# MainBoard.net
KiCad netlist of a schematic drawn in Altium Designer
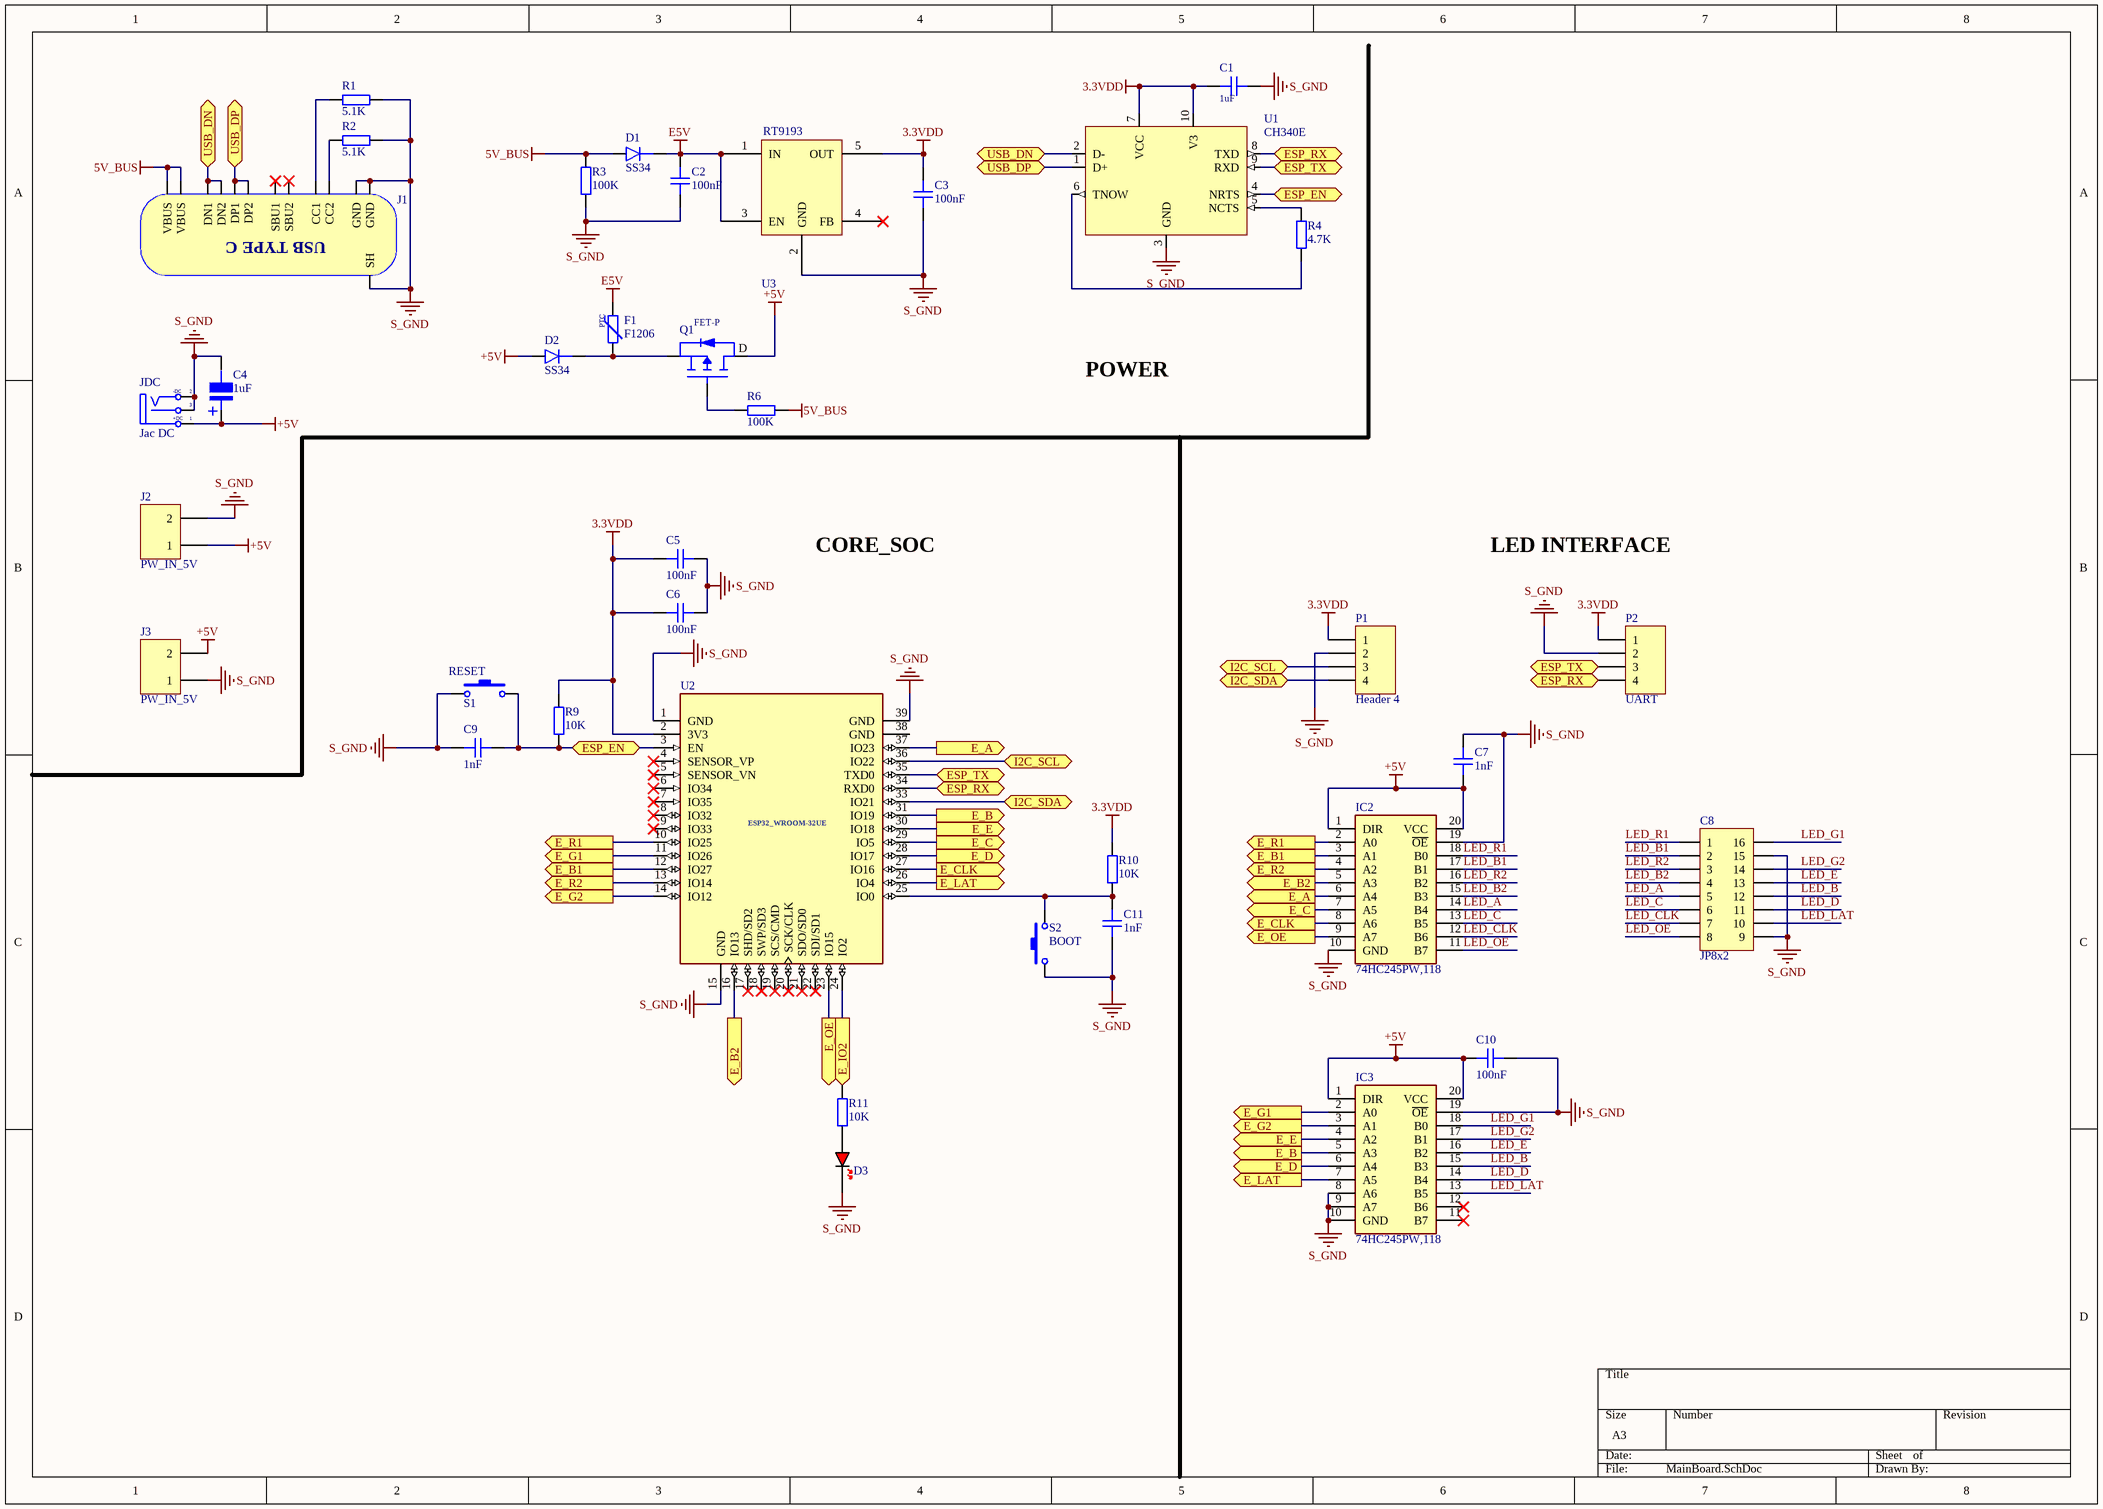
[diagram p0: MainBoard.SchDoc]

(export (version "E")
  (design (tool "Eeschema 10.0.6"))
  (components
    (comp (ref "C1")
      (value "1uF")
      (footprint "CAP_0805")
      (description "Capacitor SMD 0805 50V")
      (libsource (lib "Schematic-Lib-PhilsLab") (part "CAP_0805_50V"))
    )
    (comp (ref "C2")
      (value "100nF")
      (footprint "CAP_0603")
      (description "Capacitor SMD 0603 50V")
      (libsource (lib "Schematic-Lib-PhilsLab") (part "CAP_0603_50V"))
    )
    (comp (ref "C3")
      (value "100nF")
      (footprint "CAP_0603")
      (description "Capacitor SMD 0603 50V")
      (libsource (lib "Schematic-Lib-PhilsLab") (part "CAP_0603_50V"))
    )
    (comp (ref "C4")
      (value "1uF")
      (footprint "tu nhom 4 (B)")
      (description "Dán")
      (libsource (lib "THU VIEN SCH") (part "Tu Nhom 1uF 50V"))
    )
    (comp (ref "C5")
      (value "100nF")
      (footprint "CAP_0603")
      (description "Capacitor SMD 0603 50V")
      (libsource (lib "Schematic-Lib-PhilsLab") (part "CAP_0603_50V"))
    )
    (comp (ref "C6")
      (value "100nF")
      (footprint "CAP_0603")
      (description "Capacitor SMD 0603 50V")
      (libsource (lib "Schematic-Lib-PhilsLab") (part "CAP_0603_50V"))
    )
    (comp (ref "C7")
      (value "1nF")
      (footprint "CAP_0603")
      (description "Capacitor SMD 0603 50V")
      (libsource (lib "Schematic-Lib-PhilsLab") (part "CAP_0603_50V"))
    )
    (comp (ref "C8")
      (value "JP8x2")
      (footprint "JP8-C2T")
      (description "WR-PHD 2.54 mm Dual Socket Header")
      (fields
        (field (name "MANUFACTURER") "Würth Elektronik eiSos GmbH")
        (field (name "PARTNO") "61301621821")
        (field (name "CREATED BY") "Karrer Zheng")
      )
      (libsource (lib "My Library") (part "JP8x2"))
    )
    (comp (ref "C9")
      (value "1nF")
      (footprint "CAP_0603")
      (description "Capacitor SMD 0603 50V")
      (libsource (lib "Schematic-Lib-PhilsLab") (part "CAP_0603_50V"))
    )
    (comp (ref "C10")
      (value "100nF")
      (footprint "CAP_0603")
      (description "Capacitor SMD 0603 50V")
      (libsource (lib "Schematic-Lib-PhilsLab") (part "CAP_0603_50V"))
    )
    (comp (ref "C11")
      (value "1nF")
      (footprint "CAP_0603")
      (description "Capacitor SMD 0603 50V")
      (libsource (lib "Schematic-Lib-PhilsLab") (part "CAP_0603_50V"))
    )
    (comp (ref "D1")
      (value "SS34")
      (footprint "DO-214AC-2 (SMA)")
      (description "Diode SMD SMA (DO-214AA)")
      (libsource (lib "Schematic-Lib-PhilsLab") (part "D_SMA"))
    )
    (comp (ref "D2")
      (value "SS34")
      (footprint "DO-214AC-2 (SMA)")
      (description "Diode SMD SMA (DO-214AA)")
      (libsource (lib "Schematic-Lib-PhilsLab") (part "D_SMA"))
    )
    (comp (ref "D3")
      (value "RED")
      (footprint "LED_0603_RED")
      (description "LED 0603 RED SMD")
      (libsource (lib "Schematic-Lib-PhilsLab") (part "LED_0603_RED"))
    )
    (comp (ref "F1")
      (value "F1206")
      (footprint "FUSE_1206")
      (description "Fuse PPTC SMD 1206")
      (libsource (lib "Schematic-Lib-PhilsLab") (part "FUSE_PPTC_1206"))
    )
    (comp (ref "IC2")
      (value "74HC245PW,118")
      (footprint "74hc245pw")
      (description "Integrated Circuit")
      (fields (field (name "MOUSER PART NUMBER") "771-HC245PW118"))
      (libsource (lib "Digital_Isolator") (part "74HC245PW,118"))
    )
    (comp (ref "IC3")
      (value "74HC245PW,118")
      (footprint "74hc245pw")
      (description "Integrated Circuit")
      (fields (field (name "MOUSER PART NUMBER") "771-HC245PW118"))
      (libsource (lib "Digital_Isolator") (part "74HC245PW,118"))
    )
    (comp (ref "J1")
      (value "TYPE-C-31-M-12")
      (footprint "TYPE-C-31-M-12")
      (description "USB Type C Connector Horizontal SMT")
      (fields (field (name "MANUFACTURER") "Koren Hroparts"))
      (libsource (lib "Schematic-Lib-PhilsLab") (part "TYPE-C-31-M-12"))
    )
    (comp (ref "J2")
      (value "PW_IN_5V")
      (footprint "DOMINO 2L")
      (description "WR-TBL Terminal block - serie 311 - 5.08mm")
      (fields
        (field (name "MANUFACTURER") "Würth Elektronik eiSos GmbH")
        (field (name "PARTNO") "691311500002")
        (field (name "CREATED BY") "Karrer Zheng")
      )
      (libsource (lib "EZTOLOVE") (part "DOMINO2"))
    )
    (comp (ref "J3")
      (value "PW_IN_5V")
      (footprint "DOMINO 2L")
      (description "WR-TBL Terminal block - serie 311 - 5.08mm")
      (fields
        (field (name "MANUFACTURER") "Würth Elektronik eiSos GmbH")
        (field (name "PARTNO") "691311500002")
        (field (name "CREATED BY") "Karrer Zheng")
      )
      (libsource (lib "EZTOLOVE") (part "DOMINO2"))
    )
    (comp (ref "JDC")
      (value "Jac DC")
      (footprint "DC-IN")
      (description "Jac DC input")
      (libsource (lib "EZTOLOVE") (part "DCIN"))
    )
    (comp (ref "P1")
      (value "Header 4")
      (footprint "JP4")
      (description "Header, 4-Pin, Right Angle")
      (fields (field (name "PUBLISHER") "Altium Limited"))
      (libsource (lib "EZTOLOVE") (part "Header 4"))
    )
    (comp (ref "P2")
      (value "UART")
      (footprint "JP4")
      (description "Header, 4-Pin, Right Angle")
      (fields (field (name "PUBLISHER") "Altium Limited"))
      (libsource (lib "EZTOLOVE") (part "Header 4"))
    )
    (comp (ref "Q1")
      (value "FET-P")
      (footprint "SSM3J338R,LF-SOT23-F")
      (description "MOSFET P-Channel Vds=12V Id=6A")
      (fields
        (field (name "MANUFACTURER") "SSM3J338R,LF")
        (field (name "MANUFACTURER PART NUMBER") "Toshiba")
      )
      (libsource (lib "Schematic-Lib-PhilsLab") (part "SSM3J338R,LF"))
    )
    (comp (ref "R1")
      (value "5.1K")
      (footprint "RES_0402")
      (description "Resistor SMD 0402")
      (libsource (lib "Schematic-Lib-PhilsLab") (part "RES_0402"))
    )
    (comp (ref "R2")
      (value "5.1K")
      (footprint "RES_0402")
      (description "Resistor SMD 0402")
      (libsource (lib "Schematic-Lib-PhilsLab") (part "RES_0402"))
    )
    (comp (ref "R3")
      (value "100K")
      (footprint "RES_0402")
      (description "Resistor SMD 0402")
      (libsource (lib "Schematic-Lib-PhilsLab") (part "RES_0402"))
    )
    (comp (ref "R4")
      (value "4.7K")
      (footprint "RES_0402")
      (description "Resistor SMD 0402")
      (libsource (lib "Schematic-Lib-PhilsLab") (part "RES_0402"))
    )
    (comp (ref "R6")
      (value "100K")
      (footprint "RES_0402")
      (description "Resistor SMD 0402")
      (libsource (lib "Schematic-Lib-PhilsLab") (part "RES_0402"))
    )
    (comp (ref "R9")
      (value "10K")
      (footprint "RES_0402")
      (description "Resistor SMD 0402")
      (libsource (lib "Schematic-Lib-PhilsLab") (part "RES_0402"))
    )
    (comp (ref "R10")
      (value "10K")
      (footprint "RES_0402")
      (description "Resistor SMD 0402")
      (libsource (lib "Schematic-Lib-PhilsLab") (part "RES_0402"))
    )
    (comp (ref "R11")
      (value "10K")
      (footprint "RES_0402")
      (description "Resistor SMD 0402")
      (libsource (lib "Schematic-Lib-PhilsLab") (part "RES_0402"))
    )
    (comp (ref "S1")
      (value "RESET")
      (footprint "SW-SMD")
      (description "Switch")
      (fields (field (name "PUBLISHER") "Altium Limited"))
      (libsource (lib "My Library") (part "SW-SMD"))
    )
    (comp (ref "S2")
      (value "BOOT")
      (footprint "SW-SMD")
      (description "Switch")
      (fields (field (name "PUBLISHER") "Altium Limited"))
      (libsource (lib "My Library") (part "SW-SMD"))
    )
    (comp (ref "U1")
      (value "CH340E")
      (footprint "MSOP-10")
      (description "USB-to-UART Transceiver MSOP-10")
      (libsource (lib "Schematic-Lib-PhilsLab") (part "CH340E"))
    )
    (comp (ref "U2")
      (value "ESP32-WROOM-32D")
      (footprint "MODULE_ESP32-WROOM-32D")
      (fields (field (name "MF") "Espressif Systems"))
      (libsource (lib "Module_Core_Soc") (part "ESP32-WROOM-32D"))
    )
    (comp (ref "U3")
      (value "RT9193-33")
      (footprint "RT9193_33")
      (libsource (lib "EZTOLOVE") (part "RT9193-33"))
    )
  )
  (nets
    (net (code "1") (name "+5V") (class "Default")
      (node (ref "C10") (pin "1") (pinfunction "1_1") (pintype "passive"))
      (node (ref "C4") (pin "1") (pinfunction "1_1") (pintype "passive"))
      (node (ref "C7") (pin "2") (pinfunction "2_2") (pintype "passive"))
      (node (ref "D2") (pin "A") (pinfunction "A_A") (pintype "passive"))
      (node (ref "IC2") (pin "1") (pinfunction "DIR_1") (pintype "passive"))
      (node (ref "IC2") (pin "20") (pinfunction "VCC_20") (pintype "passive"))
      (node (ref "IC3") (pin "1") (pinfunction "DIR_1") (pintype "passive"))
      (node (ref "IC3") (pin "20") (pinfunction "VCC_20") (pintype "passive"))
      (node (ref "J2") (pin "1") (pinfunction "1_1") (pintype "passive"))
      (node (ref "J3") (pin "2") (pinfunction "2_2") (pintype "passive"))
      (node (ref "JDC") (pin "1") (pinfunction "T_1") (pintype "passive"))
      (node (ref "Q1") (pin "D") (pinfunction "D_D") (pintype "passive"))
    )
    (net (code "2") (name "/ESP_EN") (class "Default")
      (node (ref "C9") (pin "1") (pinfunction "1_1") (pintype "passive"))
      (node (ref "R9") (pin "1") (pinfunction "1_1") (pintype "passive"))
      (node (ref "S1") (pin "2") (pinfunction "2_2") (pintype "passive"))
      (node (ref "U1") (pin "4") (pinfunction "NRTS_4") (pintype "output"))
      (node (ref "U2") (pin "3") (pinfunction "EN_3") (pintype "input"))
    )
    (net (code "3") (name "/ESP_RX") (class "Default")
      (node (ref "P2") (pin "4") (pinfunction "4_4") (pintype "passive"))
      (node (ref "U1") (pin "8") (pinfunction "TXD_8") (pintype "output"))
      (node (ref "U2") (pin "34") (pinfunction "RXD0_34") (pintype "bidirectional"))
    )
    (net (code "4") (name "/ESP_TX") (class "Default")
      (node (ref "P2") (pin "3") (pinfunction "3_3") (pintype "passive"))
      (node (ref "U1") (pin "9") (pinfunction "RXD_9") (pintype "input"))
      (node (ref "U2") (pin "35") (pinfunction "TXD0_35") (pintype "bidirectional"))
    )
    (net (code "5") (name "/E_A") (class "Default")
      (node (ref "IC2") (pin "6") (pinfunction "A4_6") (pintype "passive"))
      (node (ref "U2") (pin "37") (pinfunction "IO23_37") (pintype "bidirectional"))
    )
    (net (code "6") (name "/E_B") (class "Default")
      (node (ref "IC3") (pin "5") (pinfunction "A3_5") (pintype "passive"))
      (node (ref "U2") (pin "31") (pinfunction "IO19_31") (pintype "bidirectional"))
    )
    (net (code "7") (name "/E_B1") (class "Default")
      (node (ref "IC2") (pin "3") (pinfunction "A1_3") (pintype "passive"))
      (node (ref "U2") (pin "12") (pinfunction "IO27_12") (pintype "bidirectional"))
    )
    (net (code "8") (name "/E_B2") (class "Default")
      (node (ref "IC2") (pin "5") (pinfunction "A3_5") (pintype "passive"))
      (node (ref "U2") (pin "16") (pinfunction "IO13_16") (pintype "bidirectional"))
    )
    (net (code "9") (name "/E_C") (class "Default")
      (node (ref "IC2") (pin "7") (pinfunction "A5_7") (pintype "passive"))
      (node (ref "U2") (pin "29") (pinfunction "IO5_29") (pintype "bidirectional"))
    )
    (net (code "10") (name "/E_CLK") (class "Default")
      (node (ref "IC2") (pin "8") (pinfunction "A6_8") (pintype "passive"))
      (node (ref "U2") (pin "27") (pinfunction "IO16_27") (pintype "bidirectional"))
    )
    (net (code "11") (name "/E_D") (class "Default")
      (node (ref "IC3") (pin "6") (pinfunction "A4_6") (pintype "passive"))
      (node (ref "U2") (pin "28") (pinfunction "IO17_28") (pintype "bidirectional"))
    )
    (net (code "12") (name "/E_E") (class "Default")
      (node (ref "IC3") (pin "4") (pinfunction "A2_4") (pintype "passive"))
      (node (ref "U2") (pin "30") (pinfunction "IO18_30") (pintype "bidirectional"))
    )
    (net (code "13") (name "/E_G1") (class "Default")
      (node (ref "IC3") (pin "2") (pinfunction "A0_2") (pintype "passive"))
      (node (ref "U2") (pin "11") (pinfunction "IO26_11") (pintype "bidirectional"))
    )
    (net (code "14") (name "/E_G2") (class "Default")
      (node (ref "IC3") (pin "3") (pinfunction "A1_3") (pintype "passive"))
      (node (ref "U2") (pin "14") (pinfunction "IO12_14") (pintype "bidirectional"))
    )
    (net (code "15") (name "/E_IO2") (class "Default")
      (node (ref "R11") (pin "2") (pinfunction "2_2") (pintype "passive"))
      (node (ref "U2") (pin "24") (pinfunction "IO2_24") (pintype "bidirectional"))
    )
    (net (code "16") (name "/E_LAT") (class "Default")
      (node (ref "IC3") (pin "7") (pinfunction "A5_7") (pintype "passive"))
      (node (ref "U2") (pin "26") (pinfunction "IO4_26") (pintype "bidirectional"))
    )
    (net (code "17") (name "/E_OE") (class "Default")
      (node (ref "IC2") (pin "9") (pinfunction "A7_9") (pintype "passive"))
      (node (ref "U2") (pin "23") (pinfunction "IO15_23") (pintype "bidirectional"))
    )
    (net (code "18") (name "/E_R1") (class "Default")
      (node (ref "IC2") (pin "2") (pinfunction "A0_2") (pintype "passive"))
      (node (ref "U2") (pin "10") (pinfunction "IO25_10") (pintype "bidirectional"))
    )
    (net (code "19") (name "/E_R2") (class "Default")
      (node (ref "IC2") (pin "4") (pinfunction "A2_4") (pintype "passive"))
      (node (ref "U2") (pin "13") (pinfunction "IO14_13") (pintype "bidirectional"))
    )
    (net (code "20") (name "/I2C_SCL") (class "Default")
      (node (ref "P1") (pin "3") (pinfunction "3_3") (pintype "passive"))
      (node (ref "U2") (pin "36") (pinfunction "IO22_36") (pintype "bidirectional"))
    )
    (net (code "21") (name "/I2C_SDA") (class "Default")
      (node (ref "P1") (pin "4") (pinfunction "4_4") (pintype "passive"))
      (node (ref "U2") (pin "33") (pinfunction "IO21_33") (pintype "bidirectional"))
    )
    (net (code "22") (name "/LED_A") (class "Default")
      (node (ref "C8") (pin "5") (pinfunction "5_5") (pintype "passive"))
      (node (ref "IC2") (pin "14") (pinfunction "B4_14") (pintype "passive"))
    )
    (net (code "23") (name "/LED_B") (class "Default")
      (node (ref "C8") (pin "12") (pinfunction "12_12") (pintype "passive"))
      (node (ref "IC3") (pin "15") (pinfunction "B3_15") (pintype "passive"))
    )
    (net (code "24") (name "/LED_B1") (class "Default")
      (node (ref "C8") (pin "2") (pinfunction "2_2") (pintype "passive"))
      (node (ref "IC2") (pin "17") (pinfunction "B1_17") (pintype "passive"))
    )
    (net (code "25") (name "/LED_B2") (class "Default")
      (node (ref "C8") (pin "4") (pinfunction "4_4") (pintype "passive"))
      (node (ref "IC2") (pin "15") (pinfunction "B3_15") (pintype "passive"))
    )
    (net (code "26") (name "/LED_C") (class "Default")
      (node (ref "C8") (pin "6") (pinfunction "6_6") (pintype "passive"))
      (node (ref "IC2") (pin "13") (pinfunction "B5_13") (pintype "passive"))
    )
    (net (code "27") (name "/LED_CLK") (class "Default")
      (node (ref "C8") (pin "7") (pinfunction "7_7") (pintype "passive"))
      (node (ref "IC2") (pin "12") (pinfunction "B6_12") (pintype "passive"))
    )
    (net (code "28") (name "/LED_D") (class "Default")
      (node (ref "C8") (pin "11") (pinfunction "11_11") (pintype "passive"))
      (node (ref "IC3") (pin "14") (pinfunction "B4_14") (pintype "passive"))
    )
    (net (code "29") (name "/LED_E") (class "Default")
      (node (ref "C8") (pin "13") (pinfunction "13_13") (pintype "passive"))
      (node (ref "IC3") (pin "16") (pinfunction "B2_16") (pintype "passive"))
    )
    (net (code "30") (name "/LED_G1") (class "Default")
      (node (ref "C8") (pin "16") (pinfunction "16_16") (pintype "passive"))
      (node (ref "IC3") (pin "18") (pinfunction "B0_18") (pintype "passive"))
    )
    (net (code "31") (name "/LED_G2") (class "Default")
      (node (ref "C8") (pin "14") (pinfunction "14_14") (pintype "passive"))
      (node (ref "IC3") (pin "17") (pinfunction "B1_17") (pintype "passive"))
    )
    (net (code "32") (name "/LED_LAT") (class "Default")
      (node (ref "C8") (pin "10") (pinfunction "10_10") (pintype "passive"))
      (node (ref "IC3") (pin "13") (pinfunction "B5_13") (pintype "passive"))
    )
    (net (code "33") (name "/LED_OE") (class "Default")
      (node (ref "C8") (pin "8") (pinfunction "8_8") (pintype "passive"))
      (node (ref "IC2") (pin "11") (pinfunction "B7_11") (pintype "passive"))
    )
    (net (code "34") (name "/LED_R1") (class "Default")
      (node (ref "C8") (pin "1") (pinfunction "1_1") (pintype "passive"))
      (node (ref "IC2") (pin "18") (pinfunction "B0_18") (pintype "passive"))
    )
    (net (code "35") (name "/LED_R2") (class "Default")
      (node (ref "C8") (pin "3") (pinfunction "3_3") (pintype "passive"))
      (node (ref "IC2") (pin "16") (pinfunction "B2_16") (pintype "passive"))
    )
    (net (code "36") (name "/USB_DN") (class "Default")
      (node (ref "J1") (pin "A7") (pinfunction "DN1_A7") (pintype "bidirectional"))
      (node (ref "J1") (pin "B7") (pinfunction "DN2_B7") (pintype "bidirectional"))
      (node (ref "U1") (pin "2") (pinfunction "D-_2") (pintype "bidirectional"))
    )
    (net (code "37") (name "/USB_DP") (class "Default")
      (node (ref "J1") (pin "A6") (pinfunction "DP1_A6") (pintype "bidirectional"))
      (node (ref "J1") (pin "B6") (pinfunction "DP2_B6") (pintype "bidirectional"))
      (node (ref "U1") (pin "1") (pinfunction "D+_1") (pintype "bidirectional"))
    )
    (net (code "38") (name "3.3VDD") (class "Default")
      (node (ref "C1") (pin "2") (pinfunction "2_2") (pintype "passive"))
      (node (ref "C3") (pin "2") (pinfunction "2_2") (pintype "passive"))
      (node (ref "C5") (pin "2") (pinfunction "2_2") (pintype "passive"))
      (node (ref "C6") (pin "2") (pinfunction "2_2") (pintype "passive"))
      (node (ref "P1") (pin "1") (pinfunction "1_1") (pintype "passive"))
      (node (ref "P2") (pin "1") (pinfunction "1_1") (pintype "passive"))
      (node (ref "R10") (pin "2") (pinfunction "2_2") (pintype "passive"))
      (node (ref "R9") (pin "2") (pinfunction "2_2") (pintype "passive"))
      (node (ref "U1") (pin "10") (pinfunction "V3_10") (pintype "power_in"))
      (node (ref "U1") (pin "7") (pinfunction "VCC_7") (pintype "power_in"))
      (node (ref "U2") (pin "2") (pinfunction "3V3_2") (pintype "power_in"))
      (node (ref "U3") (pin "5") (pinfunction "OUT_5") (pintype "passive"))
    )
    (net (code "39") (name "5V_BUS") (class "Default")
      (node (ref "D1") (pin "A") (pinfunction "A_A") (pintype "passive"))
      (node (ref "J1") (pin "A4B9") (pinfunction "VBUS_A4B9") (pintype "power_in"))
      (node (ref "J1") (pin "B4A9") (pinfunction "VBUS_B4A9") (pintype "power_in"))
      (node (ref "R3") (pin "2") (pinfunction "2_2") (pintype "passive"))
      (node (ref "R6") (pin "1") (pinfunction "1_1") (pintype "passive"))
    )
    (net (code "40") (name "E5V") (class "Default")
      (node (ref "C2") (pin "2") (pinfunction "2_2") (pintype "passive"))
      (node (ref "D1") (pin "K") (pinfunction "K_K") (pintype "passive"))
      (node (ref "F1") (pin "2") (pinfunction "2_2") (pintype "passive"))
      (node (ref "U3") (pin "1") (pinfunction "IN_1") (pintype "passive"))
      (node (ref "U3") (pin "3") (pinfunction "EN_3") (pintype "passive"))
    )
    (net (code "41") (name "Net-(D2-PadK)") (class "Default")
      (node (ref "D2") (pin "K") (pinfunction "K_K") (pintype "passive"))
      (node (ref "F1") (pin "1") (pinfunction "1_1") (pintype "passive"))
      (node (ref "Q1") (pin "S") (pinfunction "S_S") (pintype "passive"))
    )
    (net (code "42") (name "Net-(D3-PadA)") (class "Default")
      (node (ref "D3") (pin "A") (pinfunction "A_A") (pintype "passive"))
      (node (ref "R11") (pin "1") (pinfunction "1_1") (pintype "passive"))
    )
    (net (code "43") (name "Net-(J1-CC1)") (class "Default")
      (node (ref "J1") (pin "A5") (pinfunction "CC1_A5") (pintype "passive"))
      (node (ref "R1") (pin "1") (pinfunction "1_1") (pintype "passive"))
    )
    (net (code "44") (name "Net-(J1-CC2)") (class "Default")
      (node (ref "J1") (pin "B5") (pinfunction "CC2_B5") (pintype "tri_state"))
      (node (ref "R2") (pin "1") (pinfunction "1_1") (pintype "passive"))
    )
    (net (code "45") (name "Net-(Q1-PadG)") (class "Default")
      (node (ref "Q1") (pin "G") (pinfunction "G_G") (pintype "passive"))
      (node (ref "R6") (pin "2") (pinfunction "2_2") (pintype "passive"))
    )
    (net (code "46") (name "Net-(U1-NCTS)") (class "Default")
      (node (ref "R4") (pin "2") (pinfunction "2_2") (pintype "passive"))
      (node (ref "U1") (pin "5") (pinfunction "NCTS_5") (pintype "input"))
    )
    (net (code "47") (name "Net-(U1-TNOW)") (class "Default")
      (node (ref "R4") (pin "1") (pinfunction "1_1") (pintype "passive"))
      (node (ref "U1") (pin "6") (pinfunction "TNOW_6") (pintype "output"))
    )
    (net (code "48") (name "Net-(U2-IO0)") (class "Default")
      (node (ref "C11") (pin "1") (pinfunction "1_1") (pintype "passive"))
      (node (ref "R10") (pin "1") (pinfunction "1_1") (pintype "passive"))
      (node (ref "S2") (pin "2") (pinfunction "2_2") (pintype "passive"))
      (node (ref "U2") (pin "25") (pinfunction "IO0_25") (pintype "bidirectional"))
    )
    (net (code "49") (name "S_GND") (class "Default")
      (node (ref "C1") (pin "1") (pinfunction "1_1") (pintype "passive"))
      (node (ref "C10") (pin "2") (pinfunction "2_2") (pintype "passive"))
      (node (ref "C11") (pin "2") (pinfunction "2_2") (pintype "passive"))
      (node (ref "C2") (pin "1") (pinfunction "1_1") (pintype "passive"))
      (node (ref "C3") (pin "1") (pinfunction "1_1") (pintype "passive"))
      (node (ref "C4") (pin "2") (pinfunction "2_2") (pintype "passive"))
      (node (ref "C5") (pin "1") (pinfunction "1_1") (pintype "passive"))
      (node (ref "C6") (pin "1") (pinfunction "1_1") (pintype "passive"))
      (node (ref "C7") (pin "1") (pinfunction "1_1") (pintype "passive"))
      (node (ref "C8") (pin "15") (pinfunction "15_15") (pintype "passive"))
      (node (ref "C8") (pin "9") (pinfunction "9_9") (pintype "passive"))
      (node (ref "C9") (pin "2") (pinfunction "2_2") (pintype "passive"))
      (node (ref "D3") (pin "K") (pinfunction "K_K") (pintype "passive"))
      (node (ref "IC2") (pin "10") (pinfunction "GND_10") (pintype "passive"))
      (node (ref "IC2") (pin "19") (pinfunction "~{OE}_19") (pintype "passive"))
      (node (ref "IC3") (pin "10") (pinfunction "GND_10") (pintype "passive"))
      (node (ref "IC3") (pin "19") (pinfunction "~{OE}_19") (pintype "passive"))
      (node (ref "IC3") (pin "8") (pinfunction "A6_8") (pintype "passive"))
      (node (ref "IC3") (pin "9") (pinfunction "A7_9") (pintype "passive"))
      (node (ref "J1") (pin "A1B12") (pinfunction "GND_A1B12") (pintype "power_in"))
      (node (ref "J1") (pin "B1A12") (pinfunction "GND_B1A12") (pintype "power_in"))
      (node (ref "J1") (pin "SH") (pinfunction "SH_SH") (pintype "power_in"))
      (node (ref "J2") (pin "2") (pinfunction "2_2") (pintype "passive"))
      (node (ref "J3") (pin "1") (pinfunction "1_1") (pintype "passive"))
      (node (ref "JDC") (pin "2") (pinfunction "TN_2") (pintype "passive"))
      (node (ref "JDC") (pin "3") (pinfunction "S_3") (pintype "power_in"))
      (node (ref "P1") (pin "2") (pinfunction "2_2") (pintype "passive"))
      (node (ref "P2") (pin "2") (pinfunction "2_2") (pintype "passive"))
      (node (ref "R1") (pin "2") (pinfunction "2_2") (pintype "passive"))
      (node (ref "R2") (pin "2") (pinfunction "2_2") (pintype "passive"))
      (node (ref "R3") (pin "1") (pinfunction "1_1") (pintype "passive"))
      (node (ref "S1") (pin "1") (pinfunction "1_1") (pintype "passive"))
      (node (ref "S2") (pin "1") (pinfunction "1_1") (pintype "passive"))
      (node (ref "U1") (pin "3") (pinfunction "GND_3") (pintype "power_in"))
      (node (ref "U2") (pin "1") (pinfunction "GND_1") (pintype "power_in"))
      (node (ref "U2") (pin "15") (pinfunction "GND_15") (pintype "power_in"))
      (node (ref "U2") (pin "39") (pinfunction "GND_39") (pintype "power_in"))
      (node (ref "U3") (pin "2") (pinfunction "GND_2") (pintype "passive"))
    )
    (net (code "50") (name "unconnected-(IC3-B6-Pad12)") (class "Default")
      (node (ref "IC3") (pin "12") (pinfunction "B6_12") (pintype "passive+no_connect"))
    )
    (net (code "51") (name "unconnected-(IC3-B7-Pad11)") (class "Default")
      (node (ref "IC3") (pin "11") (pinfunction "B7_11") (pintype "passive+no_connect"))
    )
    (net (code "52") (name "unconnected-(J1-SBU1-PadA8)") (class "Default")
      (node (ref "J1") (pin "A8") (pinfunction "SBU1_A8") (pintype "bidirectional+no_connect"))
    )
    (net (code "53") (name "unconnected-(J1-SBU2-PadB8)") (class "Default")
      (node (ref "J1") (pin "B8") (pinfunction "SBU2_B8") (pintype "bidirectional+no_connect"))
    )
    (net (code "54") (name "unconnected-(U2-GND-Pad38)") (class "Default")
      (node (ref "U2") (pin "38") (pinfunction "GND_38") (pintype "power_in"))
    )
    (net (code "55") (name "unconnected-(U2-IO32-Pad8)") (class "Default")
      (node (ref "U2") (pin "8") (pinfunction "IO32_8") (pintype "bidirectional+no_connect"))
    )
    (net (code "56") (name "unconnected-(U2-IO33-Pad9)") (class "Default")
      (node (ref "U2") (pin "9") (pinfunction "IO33_9") (pintype "bidirectional+no_connect"))
    )
    (net (code "57") (name "unconnected-(U2-IO34-Pad6)") (class "Default")
      (node (ref "U2") (pin "6") (pinfunction "IO34_6") (pintype "input+no_connect"))
    )
    (net (code "58") (name "unconnected-(U2-IO35-Pad7)") (class "Default")
      (node (ref "U2") (pin "7") (pinfunction "IO35_7") (pintype "input+no_connect"))
    )
    (net (code "59") (name "unconnected-(U2-SCK{slash}CLK-Pad20)") (class "Default")
      (node (ref "U2") (pin "20") (pinfunction "SCK/CLK_20") (pintype "bidirectional+no_connect"))
    )
    (net (code "60") (name "unconnected-(U2-SCS{slash}CMD-Pad19)") (class "Default")
      (node (ref "U2") (pin "19") (pinfunction "SCS/CMD_19") (pintype "bidirectional+no_connect"))
    )
    (net (code "61") (name "unconnected-(U2-SDI{slash}SD1-Pad22)") (class "Default")
      (node (ref "U2") (pin "22") (pinfunction "SDI/SD1_22") (pintype "bidirectional+no_connect"))
    )
    (net (code "62") (name "unconnected-(U2-SDO{slash}SD0-Pad21)") (class "Default")
      (node (ref "U2") (pin "21") (pinfunction "SDO/SD0_21") (pintype "bidirectional+no_connect"))
    )
    (net (code "63") (name "unconnected-(U2-SENSOR_VN-Pad5)") (class "Default")
      (node (ref "U2") (pin "5") (pinfunction "SENSOR_VN_5") (pintype "input+no_connect"))
    )
    (net (code "64") (name "unconnected-(U2-SENSOR_VP-Pad4)") (class "Default")
      (node (ref "U2") (pin "4") (pinfunction "SENSOR_VP_4") (pintype "input+no_connect"))
    )
    (net (code "65") (name "unconnected-(U2-SHD{slash}SD2-Pad17)") (class "Default")
      (node (ref "U2") (pin "17") (pinfunction "SHD/SD2_17") (pintype "bidirectional+no_connect"))
    )
    (net (code "66") (name "unconnected-(U2-SWP{slash}SD3-Pad18)") (class "Default")
      (node (ref "U2") (pin "18") (pinfunction "SWP/SD3_18") (pintype "bidirectional+no_connect"))
    )
    (net (code "67") (name "unconnected-(U3-FB-Pad4)") (class "Default")
      (node (ref "U3") (pin "4") (pinfunction "FB_4") (pintype "passive+no_connect"))
    )
  )
)
